# Sheet2.net
KiCad netlist of a schematic drawn in Altium Designer
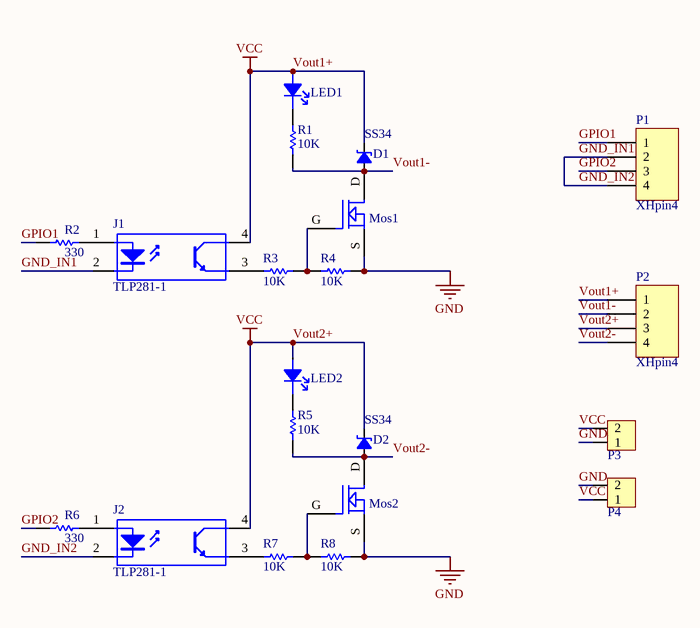
[diagram p0: Sheet2.SchDoc]

(export (version "E")
  (design (tool "Eeschema 10.0.6"))
  (components
    (comp (ref "D1")
      (value "SS34")
      (footprint "DO-214AC")
      (description "Diode")
      (libsource (lib "SCH_Active") (part "SS34"))
    )
    (comp (ref "D2")
      (value "SS34")
      (footprint "DO-214AC")
      (description "Diode")
      (libsource (lib "SCH_Active") (part "SS34"))
    )
    (comp (ref "J1")
      (value "TLP281-1")
      (footprint "TLP281-1")
      (description "光耦")
      (libsource (lib "sensor") (part "TLP281-1"))
    )
    (comp (ref "J2")
      (value "TLP281-1")
      (footprint "TLP281-1")
      (description "光耦")
      (libsource (lib "sensor") (part "TLP281-1"))
    )
    (comp (ref "LED1")
      (value "lED")
      (footprint "0805D")
      (description "LED")
      (libsource (lib "K60-mainboard-v3.1") (part "00-D-LED"))
    )
    (comp (ref "LED2")
      (value "lED")
      (footprint "0805D")
      (description "LED")
      (libsource (lib "K60-mainboard-v3.1") (part "00-D-LED"))
    )
    (comp (ref "Mos1")
      (value "MOSFET N")
      (footprint "Nmos_SOT23")
      (description "MOS SOT23")
      (libsource (lib "SCH_Active") (part "MOSFET N"))
    )
    (comp (ref "Mos2")
      (value "MOSFET N")
      (footprint "Nmos_SOT23")
      (description "MOS SOT23")
      (libsource (lib "SCH_Active") (part "MOSFET N"))
    )
    (comp (ref "P1")
      (value "XHpin4")
      (footprint "XH-2.54pin4")
      (description "XH-2.54PIN4")
      (libsource (lib "connector") (part "XH4"))
    )
    (comp (ref "P2")
      (value "XHpin4")
      (footprint "XH-2.54pin4")
      (description "XH-2.54PIN4")
      (libsource (lib "connector") (part "XH4"))
    )
    (comp (ref "P3") (value "Connector") (libsource (lib "SCH_Connector") (part "2P")))
    (comp (ref "P4") (value "Connector") (libsource (lib "SCH_Connector") (part "2P")))
    (comp (ref "R1")
      (value "10K")
      (footprint "RES-0603")
      (description "Resistor")
      (fields (field (name "Comment") "Res1") (field (name "PUBLISHER") "Altium Limited"))
      (libsource (lib "K60-mainboard-v3.1") (part "Res1"))
    )
    (comp (ref "R2")
      (value "330")
      (footprint "RES-0603")
      (description "Resistor")
      (fields (field (name "Comment") "Res1") (field (name "PUBLISHER") "Altium Limited"))
      (libsource (lib "K60-mainboard-v3.1") (part "Res1"))
    )
    (comp (ref "R3")
      (value "10K")
      (footprint "RES-0603")
      (description "Resistor")
      (fields (field (name "Comment") "Res1") (field (name "PUBLISHER") "Altium Limited"))
      (libsource (lib "K60-mainboard-v3.1") (part "Res1"))
    )
    (comp (ref "R4")
      (value "10K")
      (footprint "RES-0603")
      (description "Resistor")
      (fields (field (name "Comment") "Res1") (field (name "PUBLISHER") "Altium Limited"))
      (libsource (lib "K60-mainboard-v3.1") (part "Res1"))
    )
    (comp (ref "R5")
      (value "10K")
      (footprint "RES-0603")
      (description "Resistor")
      (fields (field (name "Comment") "Res1") (field (name "PUBLISHER") "Altium Limited"))
      (libsource (lib "K60-mainboard-v3.1") (part "Res1"))
    )
    (comp (ref "R6")
      (value "330")
      (footprint "RES-0603")
      (description "Resistor")
      (fields (field (name "Comment") "Res1") (field (name "PUBLISHER") "Altium Limited"))
      (libsource (lib "K60-mainboard-v3.1") (part "Res1"))
    )
    (comp (ref "R7")
      (value "10K")
      (footprint "RES-0603")
      (description "Resistor")
      (fields (field (name "Comment") "Res1") (field (name "PUBLISHER") "Altium Limited"))
      (libsource (lib "K60-mainboard-v3.1") (part "Res1"))
    )
    (comp (ref "R8")
      (value "10K")
      (footprint "RES-0603")
      (description "Resistor")
      (fields (field (name "Comment") "Res1") (field (name "PUBLISHER") "Altium Limited"))
      (libsource (lib "K60-mainboard-v3.1") (part "Res1"))
    )
  )
  (nets
    (net (code "1") (name "/GND_IN1") (class "Default")
      (node (ref "J1") (pin "2") (pinfunction "K_2") (pintype "passive"))
      (node (ref "J2") (pin "2") (pinfunction "K_2") (pintype "passive"))
      (node (ref "P1") (pin "2") (pinfunction "2_2") (pintype "passive"))
      (node (ref "P1") (pin "4") (pinfunction "4_4") (pintype "passive"))
    )
    (net (code "2") (name "/GPIO1") (class "Default")
      (node (ref "P1") (pin "1") (pinfunction "1_1") (pintype "passive"))
      (node (ref "R2") (pin "1") (pinfunction "1_1") (pintype "passive"))
    )
    (net (code "3") (name "/GPIO2") (class "Default")
      (node (ref "P1") (pin "3") (pinfunction "3_3") (pintype "passive"))
      (node (ref "R6") (pin "1") (pinfunction "1_1") (pintype "passive"))
    )
    (net (code "4") (name "/Vout1-") (class "Default")
      (node (ref "D1") (pin "1") (pinfunction "A_1") (pintype "passive"))
      (node (ref "Mos1") (pin "D") (pinfunction "D_D") (pintype "passive"))
      (node (ref "P2") (pin "2") (pinfunction "2_2") (pintype "passive"))
      (node (ref "R1") (pin "1") (pinfunction "1_1") (pintype "passive"))
    )
    (net (code "5") (name "/Vout2-") (class "Default")
      (node (ref "D2") (pin "1") (pinfunction "A_1") (pintype "passive"))
      (node (ref "Mos2") (pin "D") (pinfunction "D_D") (pintype "passive"))
      (node (ref "P2") (pin "4") (pinfunction "4_4") (pintype "passive"))
      (node (ref "R5") (pin "1") (pinfunction "1_1") (pintype "passive"))
    )
    (net (code "6") (name "GND") (class "Default")
      (node (ref "Mos1") (pin "S") (pinfunction "S_S") (pintype "passive"))
      (node (ref "Mos2") (pin "S") (pinfunction "S_S") (pintype "passive"))
      (node (ref "P3") (pin "1") (pinfunction "1_1") (pintype "passive"))
      (node (ref "P4") (pin "2") (pinfunction "2_2") (pintype "passive"))
      (node (ref "R4") (pin "2") (pinfunction "2_2") (pintype "passive"))
      (node (ref "R8") (pin "2") (pinfunction "2_2") (pintype "passive"))
    )
    (net (code "7") (name "Net-(J1-A)") (class "Default")
      (node (ref "J1") (pin "1") (pinfunction "A_1") (pintype "passive"))
      (node (ref "R2") (pin "2") (pinfunction "2_2") (pintype "passive"))
    )
    (net (code "8") (name "Net-(J1-E)") (class "Default")
      (node (ref "J1") (pin "3") (pinfunction "E_3") (pintype "passive"))
      (node (ref "R3") (pin "1") (pinfunction "1_1") (pintype "passive"))
    )
    (net (code "9") (name "Net-(J2-A)") (class "Default")
      (node (ref "J2") (pin "1") (pinfunction "A_1") (pintype "passive"))
      (node (ref "R6") (pin "2") (pinfunction "2_2") (pintype "passive"))
    )
    (net (code "10") (name "Net-(J2-E)") (class "Default")
      (node (ref "J2") (pin "3") (pinfunction "E_3") (pintype "passive"))
      (node (ref "R7") (pin "1") (pinfunction "1_1") (pintype "passive"))
    )
    (net (code "11") (name "Net-(LED1-2)") (class "Default")
      (node (ref "LED1") (pin "K") (pinfunction "2_K") (pintype "passive"))
      (node (ref "R1") (pin "2") (pinfunction "2_2") (pintype "passive"))
    )
    (net (code "12") (name "Net-(LED2-2)") (class "Default")
      (node (ref "LED2") (pin "K") (pinfunction "2_K") (pintype "passive"))
      (node (ref "R5") (pin "2") (pinfunction "2_2") (pintype "passive"))
    )
    (net (code "13") (name "Net-(Mos1-PadG)") (class "Default")
      (node (ref "Mos1") (pin "G") (pinfunction "G_G") (pintype "passive"))
      (node (ref "R3") (pin "2") (pinfunction "2_2") (pintype "passive"))
      (node (ref "R4") (pin "1") (pinfunction "1_1") (pintype "passive"))
    )
    (net (code "14") (name "Net-(Mos2-PadG)") (class "Default")
      (node (ref "Mos2") (pin "G") (pinfunction "G_G") (pintype "passive"))
      (node (ref "R7") (pin "2") (pinfunction "2_2") (pintype "passive"))
      (node (ref "R8") (pin "1") (pinfunction "1_1") (pintype "passive"))
    )
    (net (code "15") (name "VCC") (class "Default")
      (node (ref "D1") (pin "2") (pinfunction "K_2") (pintype "passive"))
      (node (ref "D2") (pin "2") (pinfunction "K_2") (pintype "passive"))
      (node (ref "J1") (pin "4") (pinfunction "C_4") (pintype "passive"))
      (node (ref "J2") (pin "4") (pinfunction "C_4") (pintype "passive"))
      (node (ref "LED1") (pin "A") (pinfunction "1_A") (pintype "passive"))
      (node (ref "LED2") (pin "A") (pinfunction "1_A") (pintype "passive"))
      (node (ref "P2") (pin "1") (pinfunction "1_1") (pintype "passive"))
      (node (ref "P2") (pin "3") (pinfunction "3_3") (pintype "passive"))
      (node (ref "P3") (pin "2") (pinfunction "2_2") (pintype "passive"))
      (node (ref "P4") (pin "1") (pinfunction "1_1") (pintype "passive"))
    )
  )
)
